# fpga-bank1-inside.net
KiCad netlist of a schematic drawn in Altium Designer
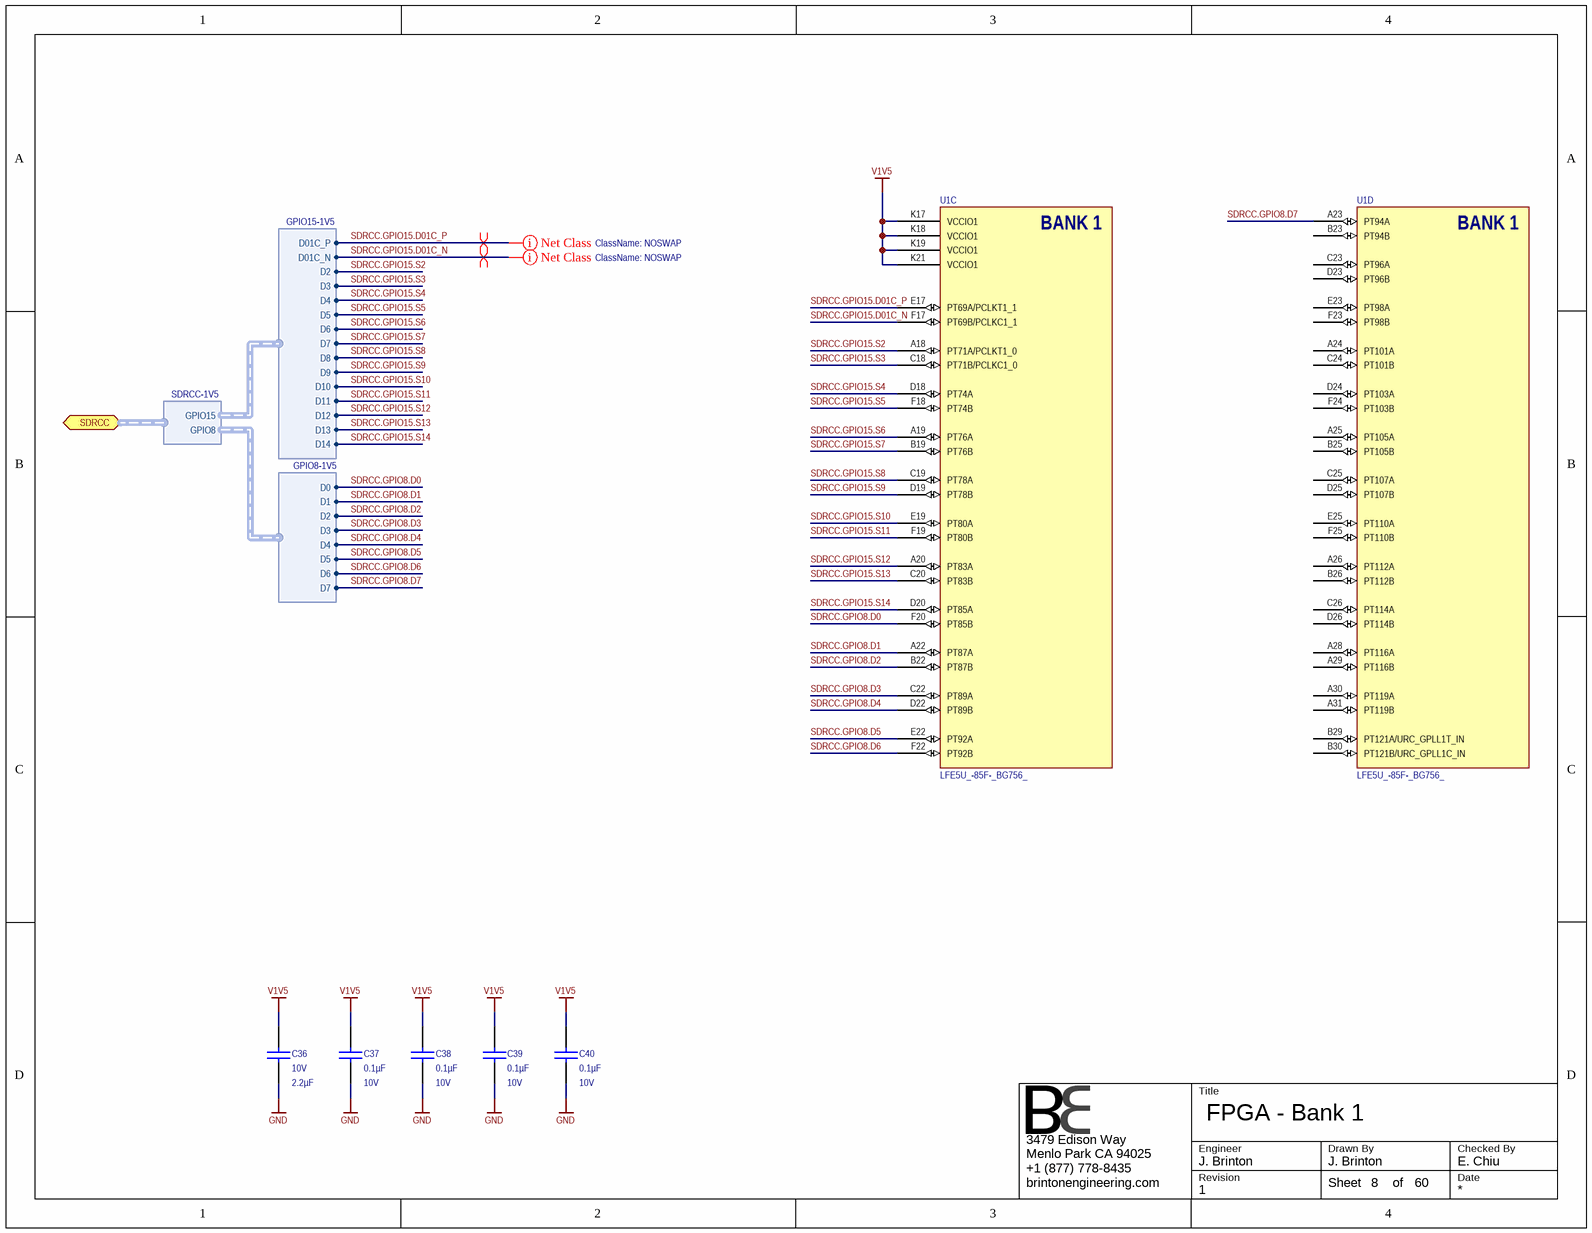
[diagram p0: fpga-bank1-inside.SchDoc]

(export (version "E")
  (design (tool "Eeschema 10.0.6"))
  (components
    (comp (ref "C36")
      (value "GRM188R71A225KE15D")
      (footprint "CAPC1608X90N")
      (description "CAP CER 2.2UF 10V 10% X7R 0603")
      (fields
        (field (name "MANUFACTURER") "Murata Electronics North America")
        (field (name "TOLERANCE") "±10%")
        (field (name "VOLTAGE - RATED") "10V")
        (field (name "CAPACITANCE") "2.2µF")
      )
      (libsource (lib "murata") (part "GRM188R71A225KE15D"))
    )
    (comp (ref "C37")
      (value "GRM155R71A104KA01J")
      (footprint "CAPC1005X56N")
      (description "CAP CER 0.1UF 10V 10% X7R 0402")
      (fields
        (field (name "MANUFACTURER") "Murata Electronics North America")
        (field (name "TOLERANCE") "±10%")
        (field (name "CAPACITANCE") "0.1µF")
        (field (name "VOLTAGE - RATED") "10V")
      )
      (libsource (lib "murata") (part "GRM155R71A104KA01J"))
    )
    (comp (ref "C38")
      (value "GRM155R71A104KA01J")
      (footprint "CAPC1005X56N")
      (description "CAP CER 0.1UF 10V 10% X7R 0402")
      (fields
        (field (name "MANUFACTURER") "Murata Electronics North America")
        (field (name "TOLERANCE") "±10%")
        (field (name "CAPACITANCE") "0.1µF")
        (field (name "VOLTAGE - RATED") "10V")
      )
      (libsource (lib "murata") (part "GRM155R71A104KA01J"))
    )
    (comp (ref "C39")
      (value "GRM155R71A104KA01J")
      (footprint "CAPC1005X56N")
      (description "CAP CER 0.1UF 10V 10% X7R 0402")
      (fields
        (field (name "MANUFACTURER") "Murata Electronics North America")
        (field (name "TOLERANCE") "±10%")
        (field (name "CAPACITANCE") "0.1µF")
        (field (name "VOLTAGE - RATED") "10V")
      )
      (libsource (lib "murata") (part "GRM155R71A104KA01J"))
    )
    (comp (ref "C40")
      (value "GRM155R71A104KA01J")
      (footprint "CAPC1005X56N")
      (description "CAP CER 0.1UF 10V 10% X7R 0402")
      (fields
        (field (name "MANUFACTURER") "Murata Electronics North America")
        (field (name "TOLERANCE") "±10%")
        (field (name "CAPACITANCE") "0.1µF")
        (field (name "VOLTAGE - RATED") "10V")
      )
      (libsource (lib "murata") (part "GRM155R71A104KA01J"))
    )
    (comp (ref "U1")
      (value "LFE5U_-85F-_BG756_")
      (footprint "lattice:caBGA756")
      (description "ECP5 FPGA, 85k LUT, 756-caBGA")
      (fields (field (name "MANUFACTURER") "Lattice Semiconductor"))
      (libsource (lib "lattice") (part "LFE5U_-85F-_BG756_"))
    )
  )
  (nets
    (net (code "3") (name "/SDRCC.GPIO8.D0") (class "Default")
      (node (ref "U1") (pin "F20") (pinfunction "PT85B_F20") (pintype "bidirectional"))
    )
    (net (code "4") (name "/SDRCC.GPIO8.D1") (class "Default")
      (node (ref "U1") (pin "A22") (pinfunction "PT87A_A22") (pintype "bidirectional"))
    )
    (net (code "5") (name "/SDRCC.GPIO8.D2") (class "Default")
      (node (ref "U1") (pin "B22") (pinfunction "PT87B_B22") (pintype "bidirectional"))
    )
    (net (code "6") (name "/SDRCC.GPIO8.D3") (class "Default")
      (node (ref "U1") (pin "C22") (pinfunction "PT89A_C22") (pintype "bidirectional"))
    )
    (net (code "7") (name "/SDRCC.GPIO8.D4") (class "Default")
      (node (ref "U1") (pin "D22") (pinfunction "PT89B_D22") (pintype "bidirectional"))
    )
    (net (code "8") (name "/SDRCC.GPIO8.D5") (class "Default")
      (node (ref "U1") (pin "E22") (pinfunction "PT92A_E22") (pintype "bidirectional"))
    )
    (net (code "9") (name "/SDRCC.GPIO8.D6") (class "Default")
      (node (ref "U1") (pin "F22") (pinfunction "PT92B_F22") (pintype "bidirectional"))
    )
    (net (code "10") (name "/SDRCC.GPIO8.D7") (class "Default")
      (node (ref "U1") (pin "A23") (pinfunction "PT94A_A23") (pintype "bidirectional"))
    )
    (net (code "11") (name "/SDRCC.GPIO15.D01C_N") (class "Default")
      (node (ref "U1") (pin "F17") (pinfunction "PT69B/PCLKC1_1_F17") (pintype "bidirectional"))
    )
    (net (code "12") (name "/SDRCC.GPIO15.D01C_P") (class "Default")
      (node (ref "U1") (pin "E17") (pinfunction "PT69A/PCLKT1_1_E17") (pintype "bidirectional"))
    )
    (net (code "13") (name "/SDRCC.GPIO15.S2") (class "Default")
      (node (ref "U1") (pin "A18") (pinfunction "PT71A/PCLKT1_0_A18") (pintype "bidirectional"))
    )
    (net (code "14") (name "/SDRCC.GPIO15.S3") (class "Default")
      (node (ref "U1") (pin "C18") (pinfunction "PT71B/PCLKC1_0_C18") (pintype "bidirectional"))
    )
    (net (code "15") (name "/SDRCC.GPIO15.S4") (class "Default")
      (node (ref "U1") (pin "D18") (pinfunction "PT74A_D18") (pintype "bidirectional"))
    )
    (net (code "16") (name "/SDRCC.GPIO15.S5") (class "Default")
      (node (ref "U1") (pin "F18") (pinfunction "PT74B_F18") (pintype "bidirectional"))
    )
    (net (code "17") (name "/SDRCC.GPIO15.S6") (class "Default")
      (node (ref "U1") (pin "A19") (pinfunction "PT76A_A19") (pintype "bidirectional"))
    )
    (net (code "18") (name "/SDRCC.GPIO15.S7") (class "Default")
      (node (ref "U1") (pin "B19") (pinfunction "PT76B_B19") (pintype "bidirectional"))
    )
    (net (code "19") (name "/SDRCC.GPIO15.S8") (class "Default")
      (node (ref "U1") (pin "C19") (pinfunction "PT78A_C19") (pintype "bidirectional"))
    )
    (net (code "20") (name "/SDRCC.GPIO15.S9") (class "Default")
      (node (ref "U1") (pin "D19") (pinfunction "PT78B_D19") (pintype "bidirectional"))
    )
    (net (code "21") (name "/SDRCC.GPIO15.S10") (class "Default")
      (node (ref "U1") (pin "E19") (pinfunction "PT80A_E19") (pintype "bidirectional"))
    )
    (net (code "22") (name "/SDRCC.GPIO15.S11") (class "Default")
      (node (ref "U1") (pin "F19") (pinfunction "PT80B_F19") (pintype "bidirectional"))
    )
    (net (code "23") (name "/SDRCC.GPIO15.S12") (class "Default")
      (node (ref "U1") (pin "A20") (pinfunction "PT83A_A20") (pintype "bidirectional"))
    )
    (net (code "24") (name "/SDRCC.GPIO15.S13") (class "Default")
      (node (ref "U1") (pin "C20") (pinfunction "PT83B_C20") (pintype "bidirectional"))
    )
    (net (code "25") (name "/SDRCC.GPIO15.S14") (class "Default")
      (node (ref "U1") (pin "D20") (pinfunction "PT85A_D20") (pintype "bidirectional"))
    )
    (net (code "28") (name "GND") (class "Default")
      (node (ref "C36") (pin "1") (pinfunction "1_1") (pintype "passive"))
      (node (ref "C37") (pin "1") (pinfunction "1_1") (pintype "passive"))
      (node (ref "C38") (pin "1") (pinfunction "1_1") (pintype "passive"))
      (node (ref "C39") (pin "1") (pinfunction "1_1") (pintype "passive"))
      (node (ref "C40") (pin "1") (pinfunction "1_1") (pintype "passive"))
    )
    (net (code "29") (name "V1V5") (class "Default")
      (node (ref "C36") (pin "2") (pinfunction "2_2") (pintype "passive"))
      (node (ref "C37") (pin "2") (pinfunction "2_2") (pintype "passive"))
      (node (ref "C38") (pin "2") (pinfunction "2_2") (pintype "passive"))
      (node (ref "C39") (pin "2") (pinfunction "2_2") (pintype "passive"))
      (node (ref "C40") (pin "2") (pinfunction "2_2") (pintype "passive"))
      (node (ref "U1") (pin "K17") (pinfunction "VCCIO1_K17") (pintype "power_in"))
      (node (ref "U1") (pin "K18") (pinfunction "VCCIO1_K18") (pintype "power_in"))
      (node (ref "U1") (pin "K19") (pinfunction "VCCIO1_K19") (pintype "power_in"))
      (node (ref "U1") (pin "K21") (pinfunction "VCCIO1_K21") (pintype "power_in"))
    )
    (net (code "30") (name "unconnected-(U1D-PT94B-PadB23)") (class "Default")
      (node (ref "U1") (pin "B23") (pinfunction "PT94B_B23") (pintype "bidirectional"))
    )
    (net (code "31") (name "unconnected-(U1D-PT96A-PadC23)") (class "Default")
      (node (ref "U1") (pin "C23") (pinfunction "PT96A_C23") (pintype "bidirectional"))
    )
    (net (code "32") (name "unconnected-(U1D-PT96B-PadD23)") (class "Default")
      (node (ref "U1") (pin "D23") (pinfunction "PT96B_D23") (pintype "bidirectional"))
    )
    (net (code "33") (name "unconnected-(U1D-PT98A-PadE23)") (class "Default")
      (node (ref "U1") (pin "E23") (pinfunction "PT98A_E23") (pintype "bidirectional"))
    )
    (net (code "34") (name "unconnected-(U1D-PT98B-PadF23)") (class "Default")
      (node (ref "U1") (pin "F23") (pinfunction "PT98B_F23") (pintype "bidirectional"))
    )
    (net (code "35") (name "unconnected-(U1D-PT101A-PadA24)") (class "Default")
      (node (ref "U1") (pin "A24") (pinfunction "PT101A_A24") (pintype "bidirectional"))
    )
    (net (code "36") (name "unconnected-(U1D-PT101B-PadC24)") (class "Default")
      (node (ref "U1") (pin "C24") (pinfunction "PT101B_C24") (pintype "bidirectional"))
    )
    (net (code "37") (name "unconnected-(U1D-PT103A-PadD24)") (class "Default")
      (node (ref "U1") (pin "D24") (pinfunction "PT103A_D24") (pintype "bidirectional"))
    )
    (net (code "38") (name "unconnected-(U1D-PT103B-PadF24)") (class "Default")
      (node (ref "U1") (pin "F24") (pinfunction "PT103B_F24") (pintype "bidirectional"))
    )
    (net (code "39") (name "unconnected-(U1D-PT105A-PadA25)") (class "Default")
      (node (ref "U1") (pin "A25") (pinfunction "PT105A_A25") (pintype "bidirectional"))
    )
    (net (code "40") (name "unconnected-(U1D-PT105B-PadB25)") (class "Default")
      (node (ref "U1") (pin "B25") (pinfunction "PT105B_B25") (pintype "bidirectional"))
    )
    (net (code "41") (name "unconnected-(U1D-PT107A-PadC25)") (class "Default")
      (node (ref "U1") (pin "C25") (pinfunction "PT107A_C25") (pintype "bidirectional"))
    )
    (net (code "42") (name "unconnected-(U1D-PT107B-PadD25)") (class "Default")
      (node (ref "U1") (pin "D25") (pinfunction "PT107B_D25") (pintype "bidirectional"))
    )
    (net (code "43") (name "unconnected-(U1D-PT110A-PadE25)") (class "Default")
      (node (ref "U1") (pin "E25") (pinfunction "PT110A_E25") (pintype "bidirectional"))
    )
    (net (code "44") (name "unconnected-(U1D-PT110B-PadF25)") (class "Default")
      (node (ref "U1") (pin "F25") (pinfunction "PT110B_F25") (pintype "bidirectional"))
    )
    (net (code "45") (name "unconnected-(U1D-PT112A-PadA26)") (class "Default")
      (node (ref "U1") (pin "A26") (pinfunction "PT112A_A26") (pintype "bidirectional"))
    )
    (net (code "46") (name "unconnected-(U1D-PT112B-PadB26)") (class "Default")
      (node (ref "U1") (pin "B26") (pinfunction "PT112B_B26") (pintype "bidirectional"))
    )
    (net (code "47") (name "unconnected-(U1D-PT114A-PadC26)") (class "Default")
      (node (ref "U1") (pin "C26") (pinfunction "PT114A_C26") (pintype "bidirectional"))
    )
    (net (code "48") (name "unconnected-(U1D-PT114B-PadD26)") (class "Default")
      (node (ref "U1") (pin "D26") (pinfunction "PT114B_D26") (pintype "bidirectional"))
    )
    (net (code "49") (name "unconnected-(U1D-PT116A-PadA28)") (class "Default")
      (node (ref "U1") (pin "A28") (pinfunction "PT116A_A28") (pintype "bidirectional"))
    )
    (net (code "50") (name "unconnected-(U1D-PT116B-PadA29)") (class "Default")
      (node (ref "U1") (pin "A29") (pinfunction "PT116B_A29") (pintype "bidirectional"))
    )
    (net (code "51") (name "unconnected-(U1D-PT119A-PadA30)") (class "Default")
      (node (ref "U1") (pin "A30") (pinfunction "PT119A_A30") (pintype "bidirectional"))
    )
    (net (code "52") (name "unconnected-(U1D-PT119B-PadA31)") (class "Default")
      (node (ref "U1") (pin "A31") (pinfunction "PT119B_A31") (pintype "bidirectional"))
    )
    (net (code "53") (name "unconnected-(U1D-PT121A{slash}URC_GPLL1T_IN-PadB29)") (class "Default")
      (node (ref "U1") (pin "B29") (pinfunction "PT121A/URC_GPLL1T_IN_B29") (pintype "bidirectional"))
    )
    (net (code "54") (name "unconnected-(U1D-PT121B{slash}URC_GPLL1C_IN-PadB30)") (class "Default")
      (node (ref "U1") (pin "B30") (pinfunction "PT121B/URC_GPLL1C_IN_B30") (pintype "bidirectional"))
    )
  )
)
